# LTE.net
KiCad netlist of a schematic drawn in Altium Designer
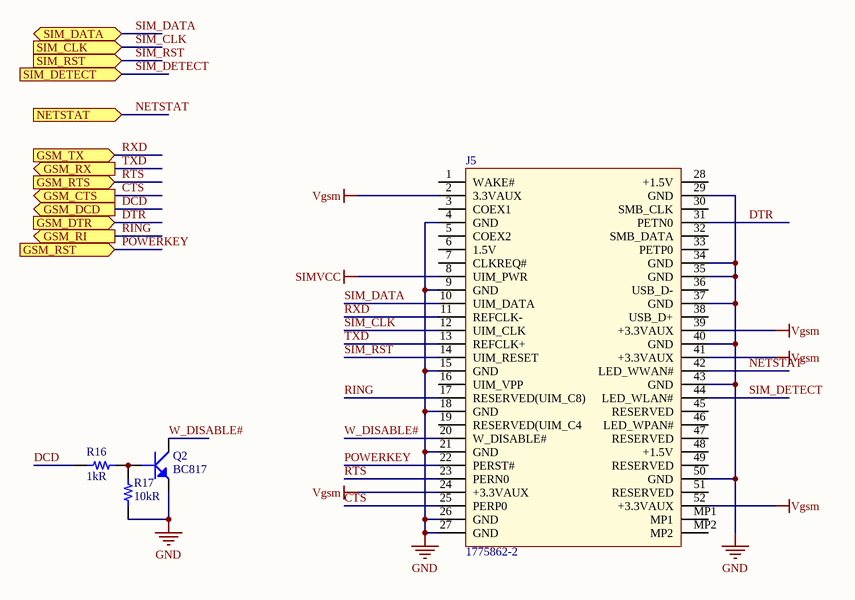
[diagram p0: LTE.SchDoc]

(export (version "E")
  (design (tool "Eeschema 10.0.6"))
  (components
    (comp (ref "J5")
      (value "1775862-2")
      (footprint "TE 1775862-2")
      (fields (field (name "MANUFACTURER") "TE Connectivity"))
      (libsource (lib "yildizIoT Library") (part "Mini PCIe"))
    )
    (comp (ref "Q2")
      (value "BC817")
      (footprint "SOT23-3")
      (description "Transistor, BC817")
      (fields
        (field (name "MANUFACTURER") "ON Semiconductor")
        (field (name "MANUFACTURER PART NUMBER") "BC817-16LT1G")
      )
      (libsource (lib "MuhammetLib") (part "BC817"))
    )
    (comp (ref "R16")
      (value "1kR")
      (footprint "RES 0603/1608")
      (description "Ceramic, SMT Capacitor")
      (fields (field (name "MANUFACTURER") "Rohm") (field (name "MANUFACTURER PART NUMBER") "ESR03EZPJ102"))
      (libsource (lib "yildizIoT Library") (part "Resistor_Chip"))
    )
    (comp (ref "R17")
      (value "10kR")
      (footprint "RES 0603/1608")
      (description "Ceramic, SMT Capacitor")
      (fields
        (field (name "MANUFACTURER") "Stackpole Electronics")
        (field (name "MANUFACTURER PART NUMBER") "RNCP0603FTD10K0")
      )
      (libsource (lib "yildizIoT Library") (part "Resistor_Chip"))
    )
  )
  (nets
    (net (code "1") (name "/CTS") (class "Default")
      (node (ref "J5") (pin "25") (pinfunction "PERP0_25") (pintype "passive"))
    )
    (net (code "2") (name "/DCD") (class "Default")
      (node (ref "R16") (pin "2") (pinfunction "2_2") (pintype "passive"))
    )
    (net (code "3") (name "/DTR") (class "Default")
      (node (ref "J5") (pin "31") (pinfunction "PETN0_31") (pintype "passive"))
    )
    (net (code "4") (name "/NETSTAT") (class "Default")
      (node (ref "J5") (pin "42") (pinfunction "LED_WWAN#_42") (pintype "passive"))
    )
    (net (code "5") (name "/POWERKEY") (class "Default")
      (node (ref "J5") (pin "22") (pinfunction "PERST#_22") (pintype "passive"))
    )
    (net (code "6") (name "/RING") (class "Default")
      (node (ref "J5") (pin "17") (pinfunction "RESERVED(UIM_C8)_17") (pintype "passive"))
    )
    (net (code "7") (name "/RTS") (class "Default")
      (node (ref "J5") (pin "23") (pinfunction "PERN0_23") (pintype "passive"))
    )
    (net (code "8") (name "/RXD") (class "Default")
      (node (ref "J5") (pin "11") (pinfunction "REFCLK-_11") (pintype "passive"))
    )
    (net (code "9") (name "/SIM_CLK") (class "Default")
      (node (ref "J5") (pin "12") (pinfunction "UIM_CLK_12") (pintype "passive"))
    )
    (net (code "10") (name "/SIM_DATA") (class "Default")
      (node (ref "J5") (pin "10") (pinfunction "UIM_DATA_10") (pintype "passive"))
    )
    (net (code "11") (name "/SIM_DETECT") (class "Default")
      (node (ref "J5") (pin "44") (pinfunction "LED_WLAN#_44") (pintype "passive"))
    )
    (net (code "12") (name "/SIM_RST") (class "Default")
      (node (ref "J5") (pin "14") (pinfunction "UIM_RESET_14") (pintype "passive"))
    )
    (net (code "13") (name "/TXD") (class "Default")
      (node (ref "J5") (pin "13") (pinfunction "REFCLK+_13") (pintype "passive"))
    )
    (net (code "14") (name "/W_DISABLE#") (class "Default")
      (node (ref "J5") (pin "20") (pinfunction "W_DISABLE#_20") (pintype "passive"))
      (node (ref "Q2") (pin "3") (pinfunction "C_3") (pintype "passive"))
    )
    (net (code "15") (name "GND") (class "Default")
      (node (ref "J5") (pin "15") (pinfunction "GND_15") (pintype "passive"))
      (node (ref "J5") (pin "18") (pinfunction "GND_18") (pintype "passive"))
      (node (ref "J5") (pin "21") (pinfunction "GND_21") (pintype "passive"))
      (node (ref "J5") (pin "26") (pinfunction "GND_26") (pintype "passive"))
      (node (ref "J5") (pin "27") (pinfunction "GND_27") (pintype "passive"))
      (node (ref "J5") (pin "29") (pinfunction "GND_29") (pintype "passive"))
      (node (ref "J5") (pin "34") (pinfunction "GND_34") (pintype "passive"))
      (node (ref "J5") (pin "35") (pinfunction "GND_35") (pintype "passive"))
      (node (ref "J5") (pin "37") (pinfunction "GND_37") (pintype "passive"))
      (node (ref "J5") (pin "4") (pinfunction "GND_4") (pintype "passive"))
      (node (ref "J5") (pin "40") (pinfunction "GND_40") (pintype "passive"))
      (node (ref "J5") (pin "43") (pinfunction "GND_43") (pintype "passive"))
      (node (ref "J5") (pin "50") (pinfunction "GND_50") (pintype "passive"))
      (node (ref "J5") (pin "9") (pinfunction "GND_9") (pintype "passive"))
      (node (ref "Q2") (pin "2") (pinfunction "E_2") (pintype "passive"))
      (node (ref "R17") (pin "1") (pinfunction "1_1") (pintype "passive"))
    )
    (net (code "16") (name "Net-(Q2-B)") (class "Default")
      (node (ref "Q2") (pin "1") (pinfunction "B_1") (pintype "passive"))
      (node (ref "R16") (pin "1") (pinfunction "1_1") (pintype "passive"))
      (node (ref "R17") (pin "2") (pinfunction "2_2") (pintype "passive"))
    )
    (net (code "17") (name "SIMVCC") (class "Default")
      (node (ref "J5") (pin "8") (pinfunction "UIM_PWR_8") (pintype "passive"))
    )
    (net (code "18") (name "Vgsm") (class "Default")
      (node (ref "J5") (pin "2") (pinfunction "3.3VAUX_2") (pintype "passive"))
      (node (ref "J5") (pin "24") (pinfunction "+3.3VAUX_24") (pintype "passive"))
      (node (ref "J5") (pin "39") (pinfunction "+3.3VAUX_39") (pintype "passive"))
      (node (ref "J5") (pin "41") (pinfunction "+3.3VAUX_41") (pintype "passive"))
      (node (ref "J5") (pin "52") (pinfunction "+3.3VAUX_52") (pintype "passive"))
    )
    (net (code "19") (name "unconnected-(J5-+1.5V-Pad28)") (class "Default")
      (node (ref "J5") (pin "28") (pinfunction "+1.5V_28") (pintype "passive"))
    )
    (net (code "20") (name "unconnected-(J5-+1.5V-Pad48)") (class "Default")
      (node (ref "J5") (pin "48") (pinfunction "+1.5V_48") (pintype "passive"))
    )
    (net (code "21") (name "unconnected-(J5-1.5V-Pad6)") (class "Default")
      (node (ref "J5") (pin "6") (pinfunction "1.5V_6") (pintype "passive"))
    )
    (net (code "22") (name "unconnected-(J5-CLKREQ#-Pad7)") (class "Default")
      (node (ref "J5") (pin "7") (pinfunction "CLKREQ#_7") (pintype "passive"))
    )
    (net (code "23") (name "unconnected-(J5-COEX1-Pad3)") (class "Default")
      (node (ref "J5") (pin "3") (pinfunction "COEX1_3") (pintype "passive"))
    )
    (net (code "24") (name "unconnected-(J5-COEX2-Pad5)") (class "Default")
      (node (ref "J5") (pin "5") (pinfunction "COEX2_5") (pintype "passive"))
    )
    (net (code "25") (name "unconnected-(J5-LED_WPAN#-Pad46)") (class "Default")
      (node (ref "J5") (pin "46") (pinfunction "LED_WPAN#_46") (pintype "passive"))
    )
    (net (code "26") (name "unconnected-(J5-PETP0-Pad33)") (class "Default")
      (node (ref "J5") (pin "33") (pinfunction "PETP0_33") (pintype "passive"))
    )
    (net (code "27") (name "unconnected-(J5-PadMP1)") (class "Default")
      (node (ref "J5") (pin "MP1") (pinfunction "MP1_MP1") (pintype "passive"))
    )
    (net (code "28") (name "unconnected-(J5-PadMP2)") (class "Default")
      (node (ref "J5") (pin "MP2") (pinfunction "MP2_MP2") (pintype "passive"))
    )
    (net (code "29") (name "unconnected-(J5-RESERVED(UIM_C4-Pad19)") (class "Default")
      (node (ref "J5") (pin "19") (pinfunction "RESERVED(UIM_C4_19") (pintype "passive"))
    )
    (net (code "30") (name "unconnected-(J5-RESERVED-Pad45)") (class "Default")
      (node (ref "J5") (pin "45") (pinfunction "RESERVED_45") (pintype "passive"))
    )
    (net (code "31") (name "unconnected-(J5-RESERVED-Pad47)") (class "Default")
      (node (ref "J5") (pin "47") (pinfunction "RESERVED_47") (pintype "passive"))
    )
    (net (code "32") (name "unconnected-(J5-RESERVED-Pad49)") (class "Default")
      (node (ref "J5") (pin "49") (pinfunction "RESERVED_49") (pintype "passive"))
    )
    (net (code "33") (name "unconnected-(J5-RESERVED-Pad51)") (class "Default")
      (node (ref "J5") (pin "51") (pinfunction "RESERVED_51") (pintype "passive"))
    )
    (net (code "34") (name "unconnected-(J5-SMB_CLK-Pad30)") (class "Default")
      (node (ref "J5") (pin "30") (pinfunction "SMB_CLK_30") (pintype "passive"))
    )
    (net (code "35") (name "unconnected-(J5-SMB_DATA-Pad32)") (class "Default")
      (node (ref "J5") (pin "32") (pinfunction "SMB_DATA_32") (pintype "passive"))
    )
    (net (code "36") (name "unconnected-(J5-UIM_VPP-Pad16)") (class "Default")
      (node (ref "J5") (pin "16") (pinfunction "UIM_VPP_16") (pintype "passive"))
    )
    (net (code "37") (name "unconnected-(J5-USB_D+-Pad38)") (class "Default")
      (node (ref "J5") (pin "38") (pinfunction "USB_D+_38") (pintype "passive"))
    )
    (net (code "38") (name "unconnected-(J5-USB_D--Pad36)") (class "Default")
      (node (ref "J5") (pin "36") (pinfunction "USB_D-_36") (pintype "passive"))
    )
    (net (code "39") (name "unconnected-(J5-WAKE#-Pad1)") (class "Default")
      (node (ref "J5") (pin "1") (pinfunction "WAKE#_1") (pintype "passive"))
    )
  )
)
